# 02_power.net
KiCad netlist of a schematic drawn in Altium Designer
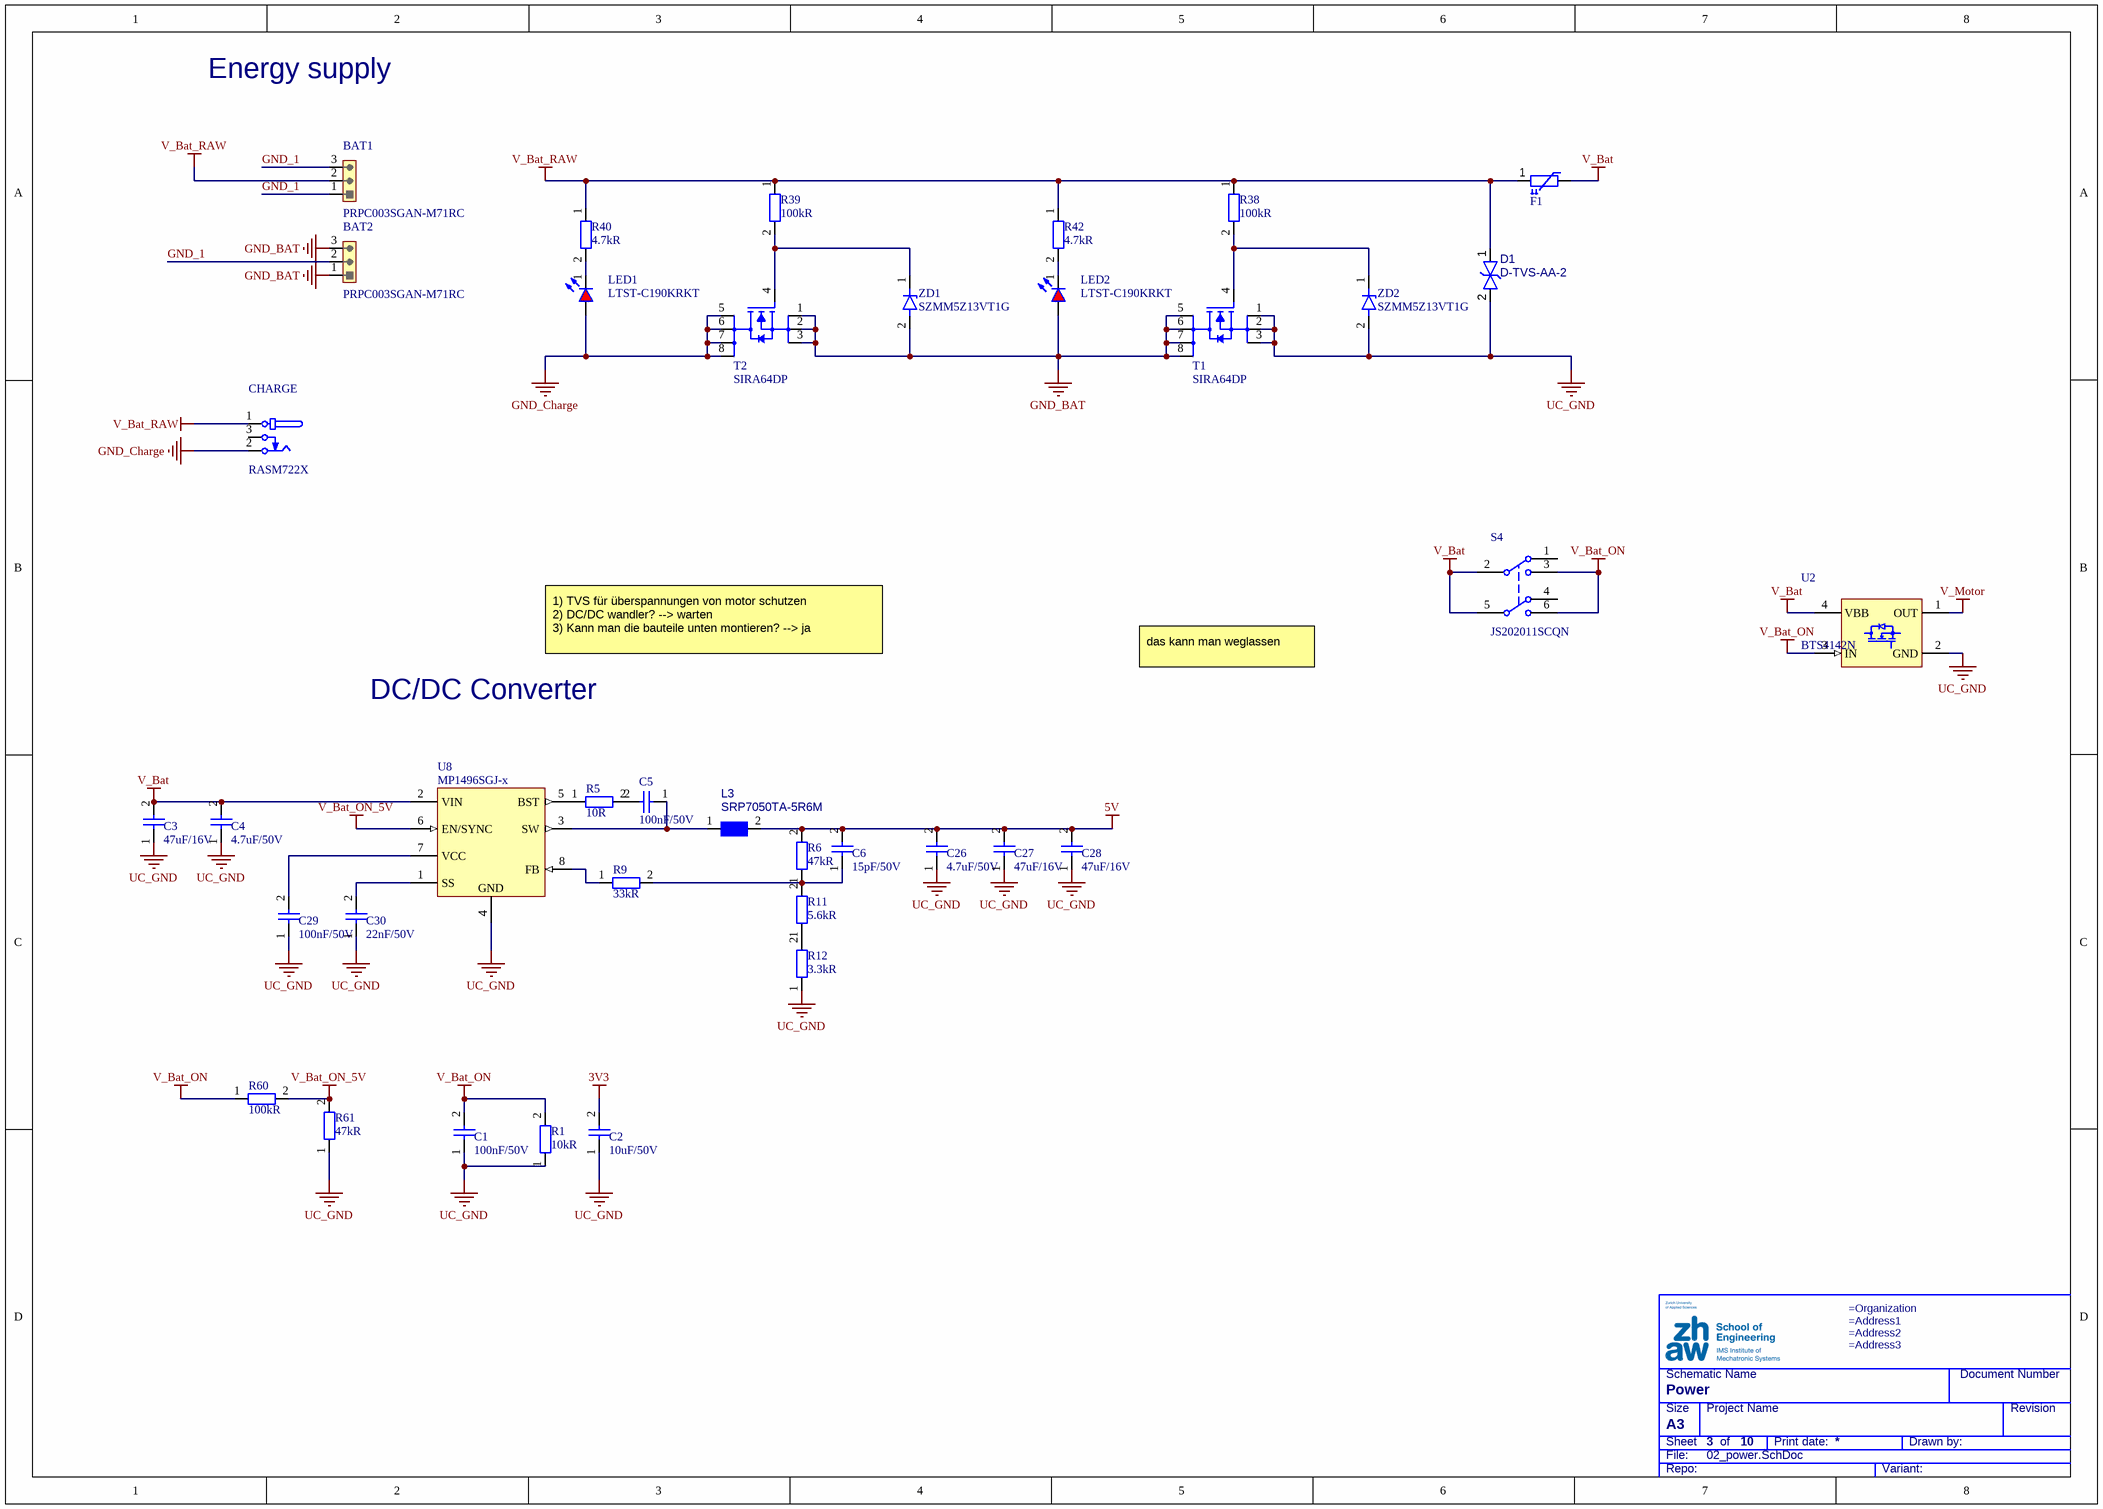
[diagram p0: 02_power.SchDoc]

(export (version "E")
  (design (tool "Eeschema 10.0.6"))
  (components
    (comp (ref "BAT1")
      (value "PRPC003SGAN-M71RC")
      (footprint "HD254_1x3_MH")
      (description "Header, 1x3Pin, Pitch 2.54mm, Male, Horizontal, THT")
      (fields (field (name "MANUFACTURER") "Sullins Connector Solutions"))
      (libsource (lib "Altium Concord Pro on Altium 365") (part "Header 1x03 m"))
    )
    (comp (ref "BAT2")
      (value "PRPC003SGAN-M71RC")
      (footprint "HD254_1x3_MH")
      (description "Header, 1x3Pin, Pitch 2.54mm, Male, Horizontal, THT")
      (fields (field (name "MANUFACTURER") "Sullins Connector Solutions"))
      (libsource (lib "Altium Concord Pro on Altium 365") (part "Header 1x03 m"))
    )
    (comp (ref "C1")
      (value "100nF/50V")
      (footprint "CAPC1005X05L")
      (description "Cap MLCC, 100nF, 50V, X7R, 10%, 0402")
      (fields (field (name "TOLERANCE") "10%"))
      (libsource (lib "Altium Concord Pro on Altium 365") (part "CAP-NP-2"))
    )
    (comp (ref "C2")
      (value "10uF/50V")
      (footprint "CAPC3216X12L")
      (description "Cap MLCC, 10uF, 50V, X5R, 10%, 1206")
      (fields (field (name "TOLERANCE") "10%"))
      (libsource (lib "Altium Concord Pro on Altium 365") (part "CAP-NP-2"))
    )
    (comp (ref "C3")
      (value "47uF/16V")
      (footprint "CAPC3225X25L")
      (description "Cap MLCC, 47uF, 16V, X5R, 20%, 1210")
      (fields (field (name "TOLERANCE") "20%"))
      (libsource (lib "Altium Concord Pro on Altium 365") (part "CAP-NP-2"))
    )
    (comp (ref "C4")
      (value "4.7uF/50V")
      (footprint "CAPC2012X15L")
      (description "Cap MLCC, 4.7uF, 50V, X5R, 10%, 0805")
      (fields (field (name "TOLERANCE") "10%"))
      (libsource (lib "Altium Concord Pro on Altium 365") (part "CAP-NP-2"))
    )
    (comp (ref "C5")
      (value "100nF/50V")
      (footprint "CAPC1005X05L")
      (description "Cap MLCC, 100nF, 50V, X7R, 10%, 0402")
      (fields (field (name "TOLERANCE") "10%"))
      (libsource (lib "Altium Concord Pro on Altium 365") (part "CAP-NP-2"))
    )
    (comp (ref "C6")
      (value "15pF/50V")
      (footprint "CAPC1005X05L")
      (description "Cap MLCC, 15pF, 50V, C0G, 5%, 0402")
      (fields (field (name "TOLERANCE") "5%"))
      (libsource (lib "Altium Concord Pro on Altium 365") (part "CAP-NP-2"))
    )
    (comp (ref "C26")
      (value "4.7uF/50V")
      (footprint "CAPC2012X15L")
      (description "Cap MLCC, 4.7uF, 50V, X5R, 10%, 0805")
      (fields (field (name "TOLERANCE") "10%"))
      (libsource (lib "Altium Concord Pro on Altium 365") (part "CAP-NP-2"))
    )
    (comp (ref "C27")
      (value "47uF/16V")
      (footprint "CAPC3225X25L")
      (description "Cap MLCC, 47uF, 16V, X5R, 20%, 1210")
      (fields (field (name "TOLERANCE") "20%"))
      (libsource (lib "Altium Concord Pro on Altium 365") (part "CAP-NP-2"))
    )
    (comp (ref "C28")
      (value "47uF/16V")
      (footprint "CAPC3225X25L")
      (description "Cap MLCC, 47uF, 16V, X5R, 20%, 1210")
      (fields (field (name "TOLERANCE") "20%"))
      (libsource (lib "Altium Concord Pro on Altium 365") (part "CAP-NP-2"))
    )
    (comp (ref "C29")
      (value "100nF/50V")
      (footprint "CAPC1005X05L")
      (description "Cap MLCC, 100nF, 50V, X7R, 10%, 0402")
      (fields (field (name "TOLERANCE") "10%"))
      (libsource (lib "Altium Concord Pro on Altium 365") (part "CAP-NP-2"))
    )
    (comp (ref "C30")
      (value "22nF/50V")
      (footprint "CAPC1005X05L")
      (description "Cap MLCC, 22nF, 50V, X7R, 10%, 0402")
      (fields (field (name "TOLERANCE") "10%"))
      (libsource (lib "Altium Concord Pro on Altium 365") (part "CAP-NP-2"))
    )
    (comp (ref "CHARGE")
      (value "RASM722X")
      (footprint "SWITCHCRAFT_RASM722X")
      (description "Barrel Power Jack, 3 Pin, Male, 5A, 250V, Horizontal, SMD, L14.5B9H11")
      (fields (field (name "MANUFACTURER") "Switchcraft"))
      (libsource (lib "Altium Concord Pro on Altium 365") (part "JACK-PWR-2C-3P-TSSWS(NC)-M"))
    )
    (comp (ref "D1")
      (value "D-TVS-AA-2")
      (footprint "DIOM4436X26L")
      (description "TVS Diode, bidirectional, 54V, 6.9A, 600W, SMB-2")
      (libsource (lib "Altium Concord Pro on Altium 365") (part "D-TVS-AA-2"))
    )
    (comp (ref "F1")
      (value "1210L050YR")
      (footprint "FUSER_1210LXXX_H85")
      (description "Resettable Fuse, Ihold 500mA, Itrip 1A, 13.2V, 1210")
      (libsource (lib "Altium Concord Pro on Altium 365") (part "RESFUSE-2"))
    )
    (comp (ref "L3")
      (value "SRP7050TA-5R6M")
      (footprint "FP-SRP7050TA-MFG")
      (description "Coil, 5.6uH, 49mR, 6A, 20%, 6A, 2626")
      (fields (field (name "TOLERANCE") "20%"))
      (libsource (lib "Altium Concord Pro on Altium 365") (part "IND-2"))
    )
    (comp (ref "LED1")
      (value "LTST-C190KRKT")
      (footprint "LEDSC160X80X80-2Lrd")
      (description "LED, Red, 20mA, 2.0V, 0603")
      (libsource (lib "Altium Concord Pro on Altium 365") (part "LED-RED-AK-2"))
    )
    (comp (ref "LED2")
      (value "LTST-C190KRKT")
      (footprint "LEDSC160X80X80-2Lrd")
      (description "LED, Red, 20mA, 2.0V, 0603")
      (libsource (lib "Altium Concord Pro on Altium 365") (part "LED-RED-AK-2"))
    )
    (comp (ref "R1")
      (value "10kR")
      (footprint "RESC1005X04L")
      (description "Res, 10kR, 1%, 0.1W, 0402")
      (fields (field (name "POWER") "100mW") (field (name "TOLERANCE") "1%"))
      (libsource (lib "") (part "RES-2_1"))
    )
    (comp (ref "R5")
      (value "10R")
      (footprint "RESC1005X04L")
      (description "Res, 10R, 1%, 0.063W, 0402")
      (fields (field (name "POWER") "63mW") (field (name "TOLERANCE") "1%"))
      (libsource (lib "Altium Concord Pro on Altium 365") (part "RES-2"))
    )
    (comp (ref "R6")
      (value "47kR")
      (footprint "RESC1005X04L")
      (description "Res, 47kR, 1%, 0.063W, 0402")
      (fields (field (name "POWER") "63mW") (field (name "TOLERANCE") "1%"))
      (libsource (lib "") (part "RES-2_1"))
    )
    (comp (ref "R9")
      (value "33kR")
      (footprint "RESC1005X04L")
      (description "Res, 33kR, 1%, 0.063W, 0402")
      (fields (field (name "POWER") "63mW") (field (name "TOLERANCE") "1%"))
      (libsource (lib "Altium Concord Pro on Altium 365") (part "RES-2"))
    )
    (comp (ref "R11")
      (value "5.6kR")
      (footprint "RESC1005X04L")
      (description "Res, 5.6kR, 1%, 0.063W, 0402")
      (fields (field (name "POWER") "63mW") (field (name "TOLERANCE") "1%"))
      (libsource (lib "") (part "RES-2_1"))
    )
    (comp (ref "R12")
      (value "3.3kR")
      (footprint "RESC1005X04L")
      (description "Res, 3.3kR, 1%, 0.063W, 0402")
      (fields (field (name "POWER") "63mW") (field (name "TOLERANCE") "1%"))
      (libsource (lib "") (part "RES-2_1"))
    )
    (comp (ref "R38")
      (value "100kR")
      (footprint "RESC1005X04L")
      (description "Res, 100kR, 1%, 0.1W, 0402")
      (fields (field (name "POWER") "100mW") (field (name "TOLERANCE") "1%"))
      (libsource (lib "") (part "RES-2_2"))
    )
    (comp (ref "R39")
      (value "100kR")
      (footprint "RESC1005X04L")
      (description "Res, 100kR, 1%, 0.1W, 0402")
      (fields (field (name "POWER") "100mW") (field (name "TOLERANCE") "1%"))
      (libsource (lib "") (part "RES-2_2"))
    )
    (comp (ref "R40")
      (value "4.7kR")
      (footprint "RESC1005X04L")
      (description "Res, 4.7kR, 1%, 0.1W, 0402")
      (fields (field (name "POWER") "100mW") (field (name "TOLERANCE") "1%"))
      (libsource (lib "") (part "RES-2_2"))
    )
    (comp (ref "R42")
      (value "4.7kR")
      (footprint "RESC1005X04L")
      (description "Res, 4.7kR, 1%, 0.1W, 0402")
      (fields (field (name "POWER") "100mW") (field (name "TOLERANCE") "1%"))
      (libsource (lib "") (part "RES-2_2"))
    )
    (comp (ref "R60")
      (value "100kR")
      (footprint "RESC1005X04L")
      (description "Res, 100kR, 1%, 0.1W, 0402")
      (fields (field (name "POWER") "100mW") (field (name "TOLERANCE") "1%"))
      (libsource (lib "Altium Concord Pro on Altium 365") (part "RES-2"))
    )
    (comp (ref "R61")
      (value "47kR")
      (footprint "RESC1005X04L")
      (description "Res, 47kR, 1%, 0.063W, 0402")
      (fields (field (name "POWER") "63mW") (field (name "TOLERANCE") "1%"))
      (libsource (lib "") (part "RES-2_1"))
    )
    (comp (ref "S4")
      (value "JS202011SCQN")
      (footprint "SW_JS202011SCQN")
      (description "Slide Switch, Vertical, DPDT, 30V, 100mA, L9B3H3.5")
      (libsource (lib "Altium Concord Pro on Altium 365") (part "SW-DPDT_6"))
    )
    (comp (ref "T1")
      (value "SIRA64DP")
      (footprint "SON127P615X515X110-8N")
      (description "MOSFET N-Enh, 30V, 60A, 100Ap, 2.1mR, 27.8W, SO-8")
      (fields (field (name "POWER") "27.8W") (field (name "VOLTAGE") "30V"))
      (libsource (lib "Altium Concord Pro on Altium 365") (part "NEMOS-SSSGDDDD-8"))
    )
    (comp (ref "T2")
      (value "SIRA64DP")
      (footprint "SON127P615X515X110-8N")
      (description "MOSFET N-Enh, 30V, 60A, 100Ap, 2.1mR, 27.8W, SO-8")
      (fields (field (name "POWER") "27.8W") (field (name "VOLTAGE") "30V"))
      (libsource (lib "Altium Concord Pro on Altium 365") (part "NEMOS-SSSGDDDD-8"))
    )
    (comp (ref "U2")
      (value "BTS4142N")
      (footprint "SOT230P700X180-4L")
      (description "High-Side Switch, 1 Ch, 12..45V, 1.4A, SOT-223-4")
      (libsource (lib "Altium Concord Pro on Altium 365") (part "BTS4142N"))
    )
    (comp (ref "U8")
      (value "MP1496SGJ-x")
      (footprint "TSOP65P280X100-8L")
      (description "Buck Converter, 0.8..15.2V, 2A, 4.5..16Vin, SOT23-8")
      (libsource (lib "ZHAW on Altium 365") (part "MP1496S"))
    )
    (comp (ref "ZD1")
      (value "SZMM5Z13VT1G")
      (footprint "SODFL160X70-2L")
      (description "Zener Diode, 13.25V±0.85V, 5mA, 30R, 500mW, SOD-523-2")
      (fields (field (name "POWER") "500mW") (field (name "VOLTAGE") "13.25V"))
      (libsource (lib "Altium Concord Pro on Altium 365") (part "D-Z-KA-2"))
    )
    (comp (ref "ZD2")
      (value "SZMM5Z13VT1G")
      (footprint "SODFL160X70-2L")
      (description "Zener Diode, 13.25V±0.85V, 5mA, 30R, 500mW, SOD-523-2")
      (fields (field (name "POWER") "500mW") (field (name "VOLTAGE") "13.25V"))
      (libsource (lib "Altium Concord Pro on Altium 365") (part "D-Z-KA-2"))
    )
  )
  (nets
    (net (code "1") (name "/GND_1") (class "Default")
      (node (ref "BAT1") (pin "1") (pinfunction "1_1") (pintype "passive"))
      (node (ref "BAT1") (pin "3") (pinfunction "3_3") (pintype "passive"))
      (node (ref "BAT2") (pin "2") (pinfunction "2_2") (pintype "passive"))
    )
    (net (code "2") (name "3V3") (class "Default")
      (node (ref "C2") (pin "2") (pinfunction "2_2") (pintype "passive"))
    )
    (net (code "3") (name "5V") (class "Default")
      (node (ref "C26") (pin "2") (pinfunction "2_2") (pintype "passive"))
      (node (ref "C27") (pin "2") (pinfunction "2_2") (pintype "passive"))
      (node (ref "C28") (pin "2") (pinfunction "2_2") (pintype "passive"))
      (node (ref "C6") (pin "2") (pinfunction "2_2") (pintype "passive"))
      (node (ref "L3") (pin "2") (pinfunction "2_2") (pintype "passive"))
      (node (ref "R6") (pin "2") (pinfunction "2_2") (pintype "passive"))
    )
    (net (code "4") (name "GND_BAT") (class "Default")
      (node (ref "BAT2") (pin "1") (pinfunction "1_1") (pintype "passive"))
      (node (ref "BAT2") (pin "3") (pinfunction "3_3") (pintype "passive"))
      (node (ref "LED2") (pin "2") (pinfunction "A_2") (pintype "passive"))
      (node (ref "T1") (pin "5") (pinfunction "D_5") (pintype "passive"))
      (node (ref "T1") (pin "6") (pinfunction "D_6") (pintype "passive"))
      (node (ref "T1") (pin "7") (pinfunction "D_7") (pintype "passive"))
      (node (ref "T1") (pin "8") (pinfunction "D_8") (pintype "passive"))
      (node (ref "T2") (pin "1") (pinfunction "S_1") (pintype "passive"))
      (node (ref "T2") (pin "2") (pinfunction "S_2") (pintype "passive"))
      (node (ref "T2") (pin "3") (pinfunction "S_3") (pintype "passive"))
      (node (ref "ZD1") (pin "2") (pinfunction "Anode_2") (pintype "passive"))
    )
    (net (code "5") (name "GND_Charge") (class "Default")
      (node (ref "CHARGE") (pin "2") (pinfunction "TIP_2") (pintype "passive"))
      (node (ref "LED1") (pin "2") (pinfunction "A_2") (pintype "passive"))
      (node (ref "T2") (pin "5") (pinfunction "D_5") (pintype "passive"))
      (node (ref "T2") (pin "6") (pinfunction "D_6") (pintype "passive"))
      (node (ref "T2") (pin "7") (pinfunction "D_7") (pintype "passive"))
      (node (ref "T2") (pin "8") (pinfunction "D_8") (pintype "passive"))
    )
    (net (code "6") (name "Net-(C5-Pad2)") (class "Default")
      (node (ref "C5") (pin "2") (pinfunction "2_2") (pintype "passive"))
      (node (ref "R5") (pin "2") (pinfunction "2_2") (pintype "passive"))
    )
    (net (code "7") (name "Net-(C6-Pad1)") (class "Default")
      (node (ref "C6") (pin "1") (pinfunction "1_1") (pintype "passive"))
      (node (ref "R11") (pin "2") (pinfunction "2_2") (pintype "passive"))
      (node (ref "R6") (pin "1") (pinfunction "1_1") (pintype "passive"))
      (node (ref "R9") (pin "2") (pinfunction "2_2") (pintype "passive"))
    )
    (net (code "8") (name "Net-(LED1-K)") (class "Default")
      (node (ref "LED1") (pin "1") (pinfunction "K_1") (pintype "passive"))
      (node (ref "R40") (pin "2") (pinfunction "2_2") (pintype "passive"))
    )
    (net (code "9") (name "Net-(LED2-K)") (class "Default")
      (node (ref "LED2") (pin "1") (pinfunction "K_1") (pintype "passive"))
      (node (ref "R42") (pin "2") (pinfunction "2_2") (pintype "passive"))
    )
    (net (code "10") (name "Net-(R11-Pad1)") (class "Default")
      (node (ref "R11") (pin "1") (pinfunction "1_1") (pintype "passive"))
      (node (ref "R12") (pin "2") (pinfunction "2_2") (pintype "passive"))
    )
    (net (code "11") (name "Net-(T1-G)") (class "Default")
      (node (ref "R38") (pin "2") (pinfunction "2_2") (pintype "passive"))
      (node (ref "T1") (pin "4") (pinfunction "G_4") (pintype "passive"))
      (node (ref "ZD2") (pin "1") (pinfunction "Cathode_1") (pintype "passive"))
    )
    (net (code "12") (name "Net-(T2-G)") (class "Default")
      (node (ref "R39") (pin "2") (pinfunction "2_2") (pintype "passive"))
      (node (ref "T2") (pin "4") (pinfunction "G_4") (pintype "passive"))
      (node (ref "ZD1") (pin "1") (pinfunction "Cathode_1") (pintype "passive"))
    )
    (net (code "13") (name "Net-(U8-BST)") (class "Default")
      (node (ref "R5") (pin "1") (pinfunction "1_1") (pintype "passive"))
      (node (ref "U8") (pin "5") (pinfunction "BST_5") (pintype "output"))
    )
    (net (code "14") (name "Net-(U8-FB)") (class "Default")
      (node (ref "R9") (pin "1") (pinfunction "1_1") (pintype "passive"))
      (node (ref "U8") (pin "8") (pinfunction "FB_8") (pintype "input"))
    )
    (net (code "15") (name "Net-(U8-SS)") (class "Default")
      (node (ref "C30") (pin "2") (pinfunction "2_2") (pintype "passive"))
      (node (ref "U8") (pin "1") (pinfunction "SS_1") (pintype "passive"))
    )
    (net (code "16") (name "Net-(U8-SW)") (class "Default")
      (node (ref "C5") (pin "1") (pinfunction "1_1") (pintype "passive"))
      (node (ref "L3") (pin "1") (pinfunction "1_1") (pintype "passive"))
      (node (ref "U8") (pin "3") (pinfunction "SW_3") (pintype "output"))
    )
    (net (code "17") (name "Net-(U8-VCC)") (class "Default")
      (node (ref "C29") (pin "2") (pinfunction "2_2") (pintype "passive"))
      (node (ref "U8") (pin "7") (pinfunction "VCC_7") (pintype "passive"))
    )
    (net (code "18") (name "UC_GND") (class "Default")
      (node (ref "C1") (pin "1") (pinfunction "1_1") (pintype "passive"))
      (node (ref "C2") (pin "1") (pinfunction "1_1") (pintype "passive"))
      (node (ref "C26") (pin "1") (pinfunction "1_1") (pintype "passive"))
      (node (ref "C27") (pin "1") (pinfunction "1_1") (pintype "passive"))
      (node (ref "C28") (pin "1") (pinfunction "1_1") (pintype "passive"))
      (node (ref "C29") (pin "1") (pinfunction "1_1") (pintype "passive"))
      (node (ref "C3") (pin "1") (pinfunction "1_1") (pintype "passive"))
      (node (ref "C30") (pin "1") (pinfunction "1_1") (pintype "passive"))
      (node (ref "C4") (pin "1") (pinfunction "1_1") (pintype "passive"))
      (node (ref "D1") (pin "2") (pinfunction "A_2") (pintype "passive"))
      (node (ref "R1") (pin "1") (pinfunction "1_1") (pintype "passive"))
      (node (ref "R12") (pin "1") (pinfunction "1_1") (pintype "passive"))
      (node (ref "R61") (pin "1") (pinfunction "1_1") (pintype "passive"))
      (node (ref "T1") (pin "1") (pinfunction "S_1") (pintype "passive"))
      (node (ref "T1") (pin "2") (pinfunction "S_2") (pintype "passive"))
      (node (ref "T1") (pin "3") (pinfunction "S_3") (pintype "passive"))
      (node (ref "U2") (pin "2") (pinfunction "GND_2") (pintype "power_in"))
      (node (ref "U8") (pin "4") (pinfunction "GND_4") (pintype "power_in"))
      (node (ref "ZD2") (pin "2") (pinfunction "Anode_2") (pintype "passive"))
    )
    (net (code "19") (name "V_Bat") (class "Default")
      (node (ref "C3") (pin "2") (pinfunction "2_2") (pintype "passive"))
      (node (ref "C4") (pin "2") (pinfunction "2_2") (pintype "passive"))
      (node (ref "F1") (pin "2") (pinfunction "2_2") (pintype "passive"))
      (node (ref "S4") (pin "2") (pinfunction "2_2") (pintype "passive"))
      (node (ref "S4") (pin "5") (pinfunction "5_5") (pintype "passive"))
      (node (ref "U2") (pin "4") (pinfunction "VBB_4") (pintype "power_in"))
      (node (ref "U8") (pin "2") (pinfunction "VIN_2") (pintype "power_in"))
    )
    (net (code "20") (name "V_Bat_ON") (class "Default")
      (node (ref "C1") (pin "2") (pinfunction "2_2") (pintype "passive"))
      (node (ref "R1") (pin "2") (pinfunction "2_2") (pintype "passive"))
      (node (ref "R60") (pin "1") (pinfunction "1_1") (pintype "passive"))
      (node (ref "S4") (pin "3") (pinfunction "3_3") (pintype "passive"))
      (node (ref "S4") (pin "6") (pinfunction "6_6") (pintype "passive"))
      (node (ref "U2") (pin "3") (pinfunction "IN_3") (pintype "input"))
    )
    (net (code "21") (name "V_Bat_ON_5V") (class "Default")
      (node (ref "R60") (pin "2") (pinfunction "2_2") (pintype "passive"))
      (node (ref "R61") (pin "2") (pinfunction "2_2") (pintype "passive"))
      (node (ref "U8") (pin "6") (pinfunction "EN/SYNC_6") (pintype "input"))
    )
    (net (code "22") (name "V_Bat_RAW") (class "Default")
      (node (ref "BAT1") (pin "2") (pinfunction "2_2") (pintype "passive"))
      (node (ref "CHARGE") (pin "1") (pinfunction "SLEEVE_1") (pintype "passive"))
      (node (ref "D1") (pin "1") (pinfunction "A_1") (pintype "passive"))
      (node (ref "F1") (pin "1") (pinfunction "1_1") (pintype "passive"))
      (node (ref "R38") (pin "1") (pinfunction "1_1") (pintype "passive"))
      (node (ref "R39") (pin "1") (pinfunction "1_1") (pintype "passive"))
      (node (ref "R40") (pin "1") (pinfunction "1_1") (pintype "passive"))
      (node (ref "R42") (pin "1") (pinfunction "1_1") (pintype "passive"))
    )
    (net (code "23") (name "V_Motor") (class "Default")
      (node (ref "U2") (pin "1") (pinfunction "OUT_1") (pintype "power_in"))
    )
    (net (code "24") (name "unconnected-(CHARGE-SHUNT-Pad3)") (class "Default")
      (node (ref "CHARGE") (pin "3") (pinfunction "SHUNT_3") (pintype "passive"))
    )
    (net (code "25") (name "unconnected-(S4-Pad1)") (class "Default")
      (node (ref "S4") (pin "1") (pinfunction "1_1") (pintype "passive"))
    )
    (net (code "26") (name "unconnected-(S4-Pad4)") (class "Default")
      (node (ref "S4") (pin "4") (pinfunction "4_4") (pintype "passive"))
    )
  )
)
